# webcam_with_pan_tilt.net
KiCad netlist of a schematic drawn in EAGLE
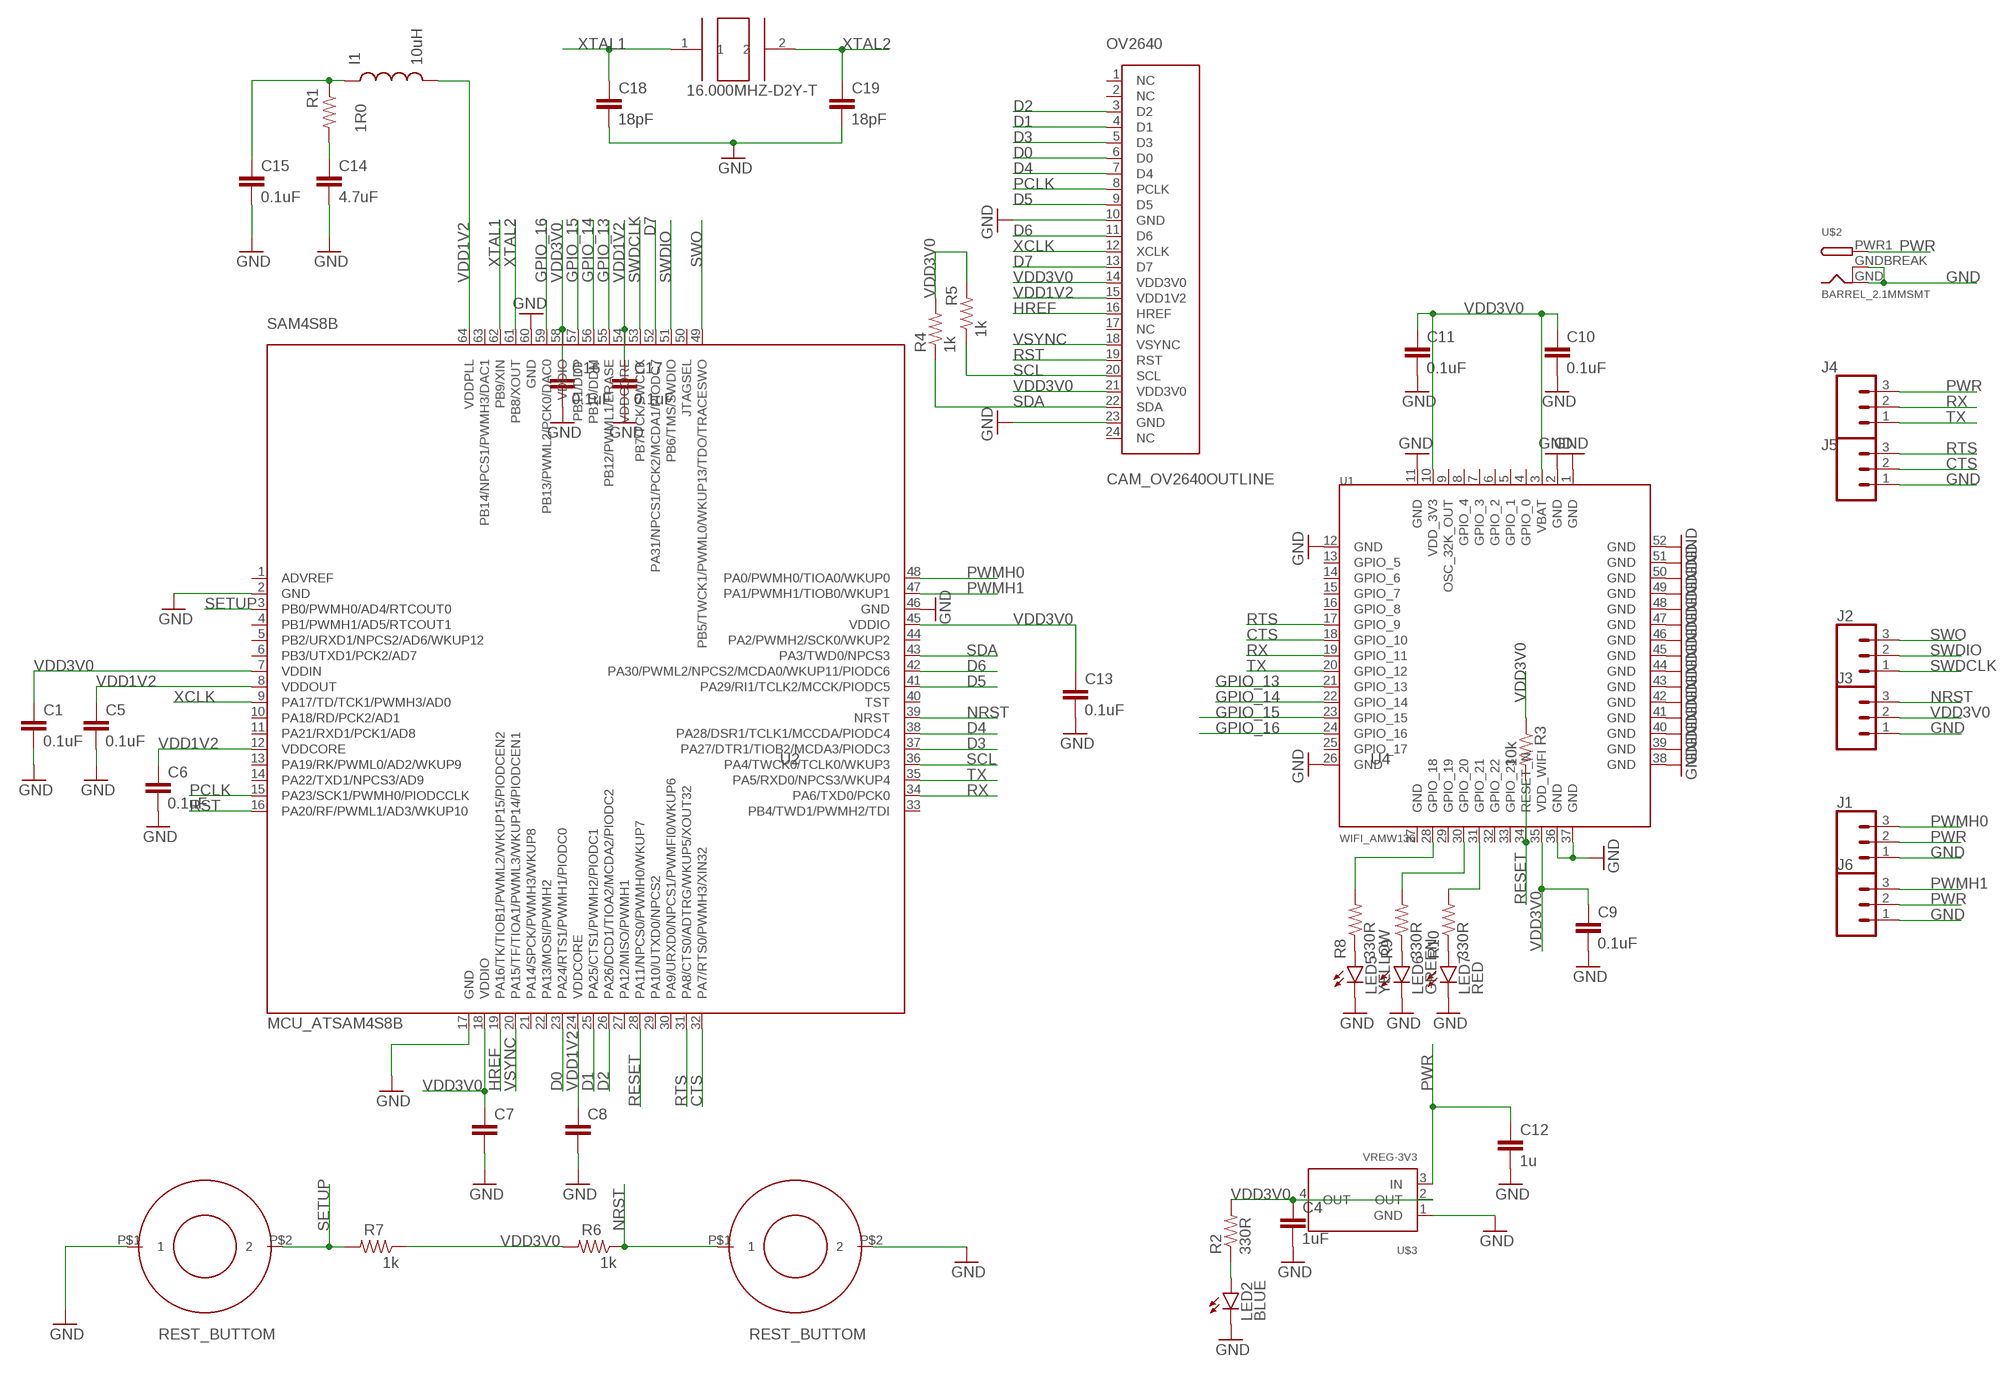
[diagram p0: schematic, sheet 1]

(export (version "E")
  (design (tool "Eeschema 10.0.6"))
  (components
    (comp (ref "16.000MHZ-D2Y-T")
      (value "XTAL_12MHZ")
      (footprint "eagle-import:ABM7-16.000MHZ-D2Y-T")
      (libsource (lib "eagle-import") (part "XTAL_12MHZ"))
    )
    (comp (ref "C1")
      (value "0.1uF")
      (footprint "eagle-import:0805")
      (libsource (lib "eagle-import") (part "CAP"))
    )
    (comp (ref "C4")
      (value "1uF")
      (footprint "eagle-import:0805")
      (libsource (lib "eagle-import") (part "CAP"))
    )
    (comp (ref "C5")
      (value "0.1uF")
      (footprint "eagle-import:0805")
      (libsource (lib "eagle-import") (part "CAP"))
    )
    (comp (ref "C6")
      (value "0.1uF")
      (footprint "eagle-import:0805")
      (libsource (lib "eagle-import") (part "CAP"))
    )
    (comp (ref "C7")
      (value "CAP")
      (footprint "eagle-import:0805")
      (libsource (lib "eagle-import") (part "CAP"))
    )
    (comp (ref "C8")
      (value "CAP")
      (footprint "eagle-import:0805")
      (libsource (lib "eagle-import") (part "CAP"))
    )
    (comp (ref "C9")
      (value "0.1uF")
      (footprint "eagle-import:0805")
      (libsource (lib "eagle-import") (part "CAP"))
    )
    (comp (ref "C10")
      (value "0.1uF")
      (footprint "eagle-import:0805")
      (libsource (lib "eagle-import") (part "CAP"))
    )
    (comp (ref "C11")
      (value "0.1uF")
      (footprint "eagle-import:0805")
      (libsource (lib "eagle-import") (part "CAP"))
    )
    (comp (ref "C12")
      (value "1u")
      (footprint "eagle-import:0805")
      (libsource (lib "eagle-import") (part "CAP"))
    )
    (comp (ref "C13")
      (value "0.1uF")
      (footprint "eagle-import:0805")
      (libsource (lib "eagle-import") (part "CAP"))
    )
    (comp (ref "C14")
      (value "4.7uF")
      (footprint "eagle-import:0805")
      (libsource (lib "eagle-import") (part "CAP"))
    )
    (comp (ref "C15")
      (value "0.1uF")
      (footprint "eagle-import:0805")
      (libsource (lib "eagle-import") (part "CAP"))
    )
    (comp (ref "C16")
      (value "0.1uF")
      (footprint "eagle-import:0805")
      (libsource (lib "eagle-import") (part "CAP"))
    )
    (comp (ref "C17")
      (value "0.1uF")
      (footprint "eagle-import:0805")
      (libsource (lib "eagle-import") (part "CAP"))
    )
    (comp (ref "C18")
      (value "18pF")
      (footprint "eagle-import:0805")
      (libsource (lib "eagle-import") (part "CAP"))
    )
    (comp (ref "C19")
      (value "18pF")
      (footprint "eagle-import:0805")
      (libsource (lib "eagle-import") (part "CAP"))
    )
    (comp (ref "I1")
      (value "10uH")
      (footprint "eagle-import:0805")
      (libsource (lib "eagle-import") (part "IND"))
    )
    (comp (ref "J1")
      (value "CONN_03")
      (footprint "eagle-import:1X03")
      (libsource (lib "eagle-import") (part "CONN_03"))
    )
    (comp (ref "J2")
      (value "CONN_03")
      (footprint "eagle-import:1X03")
      (libsource (lib "eagle-import") (part "CONN_03"))
    )
    (comp (ref "J3")
      (value "CONN_03")
      (footprint "eagle-import:1X03")
      (libsource (lib "eagle-import") (part "CONN_03"))
    )
    (comp (ref "J4")
      (value "CONN_03")
      (footprint "eagle-import:1X03")
      (libsource (lib "eagle-import") (part "CONN_03"))
    )
    (comp (ref "J5")
      (value "CONN_03")
      (footprint "eagle-import:1X03")
      (libsource (lib "eagle-import") (part "CONN_03"))
    )
    (comp (ref "J6")
      (value "CONN_03")
      (footprint "eagle-import:1X03")
      (libsource (lib "eagle-import") (part "CONN_03"))
    )
    (comp (ref "LED2")
      (value "BLUE")
      (footprint "eagle-import:LED-0603")
      (libsource (lib "eagle-import") (part "LED0603"))
    )
    (comp (ref "LED5")
      (value "YELLOW")
      (footprint "eagle-import:LED-0603")
      (libsource (lib "eagle-import") (part "LED0603"))
    )
    (comp (ref "LED6")
      (value "GREEN")
      (footprint "eagle-import:LED-0603")
      (libsource (lib "eagle-import") (part "LED0603"))
    )
    (comp (ref "LED7")
      (value "RED")
      (footprint "eagle-import:LED-0603")
      (libsource (lib "eagle-import") (part "LED0603"))
    )
    (comp (ref "OV2640")
      (value "CAM_OV2640OUTLINE")
      (footprint "eagle-import:CAM_CONN")
      (libsource (lib "eagle-import") (part "CAM_OV2640OUTLINE"))
    )
    (comp (ref "R1")
      (value "1R0")
      (footprint "eagle-import:0805")
      (libsource (lib "eagle-import") (part "RES"))
    )
    (comp (ref "R2")
      (value "330R")
      (footprint "eagle-import:0805")
      (libsource (lib "eagle-import") (part "RES"))
    )
    (comp (ref "R3")
      (value "10k")
      (footprint "eagle-import:0805")
      (libsource (lib "eagle-import") (part "RES"))
    )
    (comp (ref "R4")
      (value "1k")
      (footprint "eagle-import:0805")
      (libsource (lib "eagle-import") (part "RES"))
    )
    (comp (ref "R5")
      (value "1k")
      (footprint "eagle-import:0805")
      (libsource (lib "eagle-import") (part "RES"))
    )
    (comp (ref "R6")
      (value "1k")
      (footprint "eagle-import:0805")
      (libsource (lib "eagle-import") (part "RES"))
    )
    (comp (ref "R7")
      (value "1k")
      (footprint "eagle-import:0805")
      (libsource (lib "eagle-import") (part "RES"))
    )
    (comp (ref "R8")
      (value "330R")
      (footprint "eagle-import:0805")
      (libsource (lib "eagle-import") (part "RES"))
    )
    (comp (ref "R9")
      (value "330R")
      (footprint "eagle-import:0805")
      (libsource (lib "eagle-import") (part "RES"))
    )
    (comp (ref "R10")
      (value "330R")
      (footprint "eagle-import:0805")
      (libsource (lib "eagle-import") (part "RES"))
    )
    (comp (ref "SAM4S8B")
      (value "MCU_ATSAM4S8B")
      (footprint "eagle-import:QFP50P1200X1200X160-64N")
      (libsource (lib "eagle-import") (part "MCU_ATSAM4S8B"))
    )
    (comp (ref "U$2")
      (value "BARREL_2.1MMSMT")
      (footprint "eagle-import:DCJACK_2MM_SMT")
      (libsource (lib "eagle-import") (part "BARREL_2.1MMSMT"))
    )
    (comp (ref "U$3")
      (value "VREG-3V3")
      (footprint "eagle-import:R-PDSO-G4_TI")
      (libsource (lib "eagle-import") (part "VREG-3V3"))
    )
    (comp (ref "U1")
      (value "WIFI_AMW136")
      (footprint "eagle-import:AMW136")
      (libsource (lib "eagle-import") (part "WIFI_AMW136"))
    )
    (comp (ref "U2")
      (value "REST_BUTTOM")
      (footprint "eagle-import:BTN_2")
      (libsource (lib "eagle-import") (part "SWITCH_BTN_NO"))
    )
    (comp (ref "U4")
      (value "REST_BUTTOM")
      (footprint "eagle-import:BTN_2")
      (libsource (lib "eagle-import") (part "SWITCH_BTN_NO"))
    )
  )
  (nets
    (net (code "1") (name "/CTS") (class "Default")
      (node (ref "J5") (pin "2") (pinfunction "2_2") (pintype "passive"))
      (node (ref "SAM4S8B") (pin "32") (pinfunction "PA7/RTS0/PWMH3/XIN32_32") (pintype "bidirectional"))
      (node (ref "U1") (pin "18") (pinfunction "GPIO_10_18") (pintype "bidirectional"))
    )
    (net (code "2") (name "/D0") (class "Default")
      (node (ref "OV2640") (pin "6") (pinfunction "D0_6") (pintype "bidirectional"))
      (node (ref "SAM4S8B") (pin "23") (pinfunction "PA24/RTS1/PWMH1/PIODC0_23") (pintype "bidirectional"))
    )
    (net (code "3") (name "/D1") (class "Default")
      (node (ref "OV2640") (pin "4") (pinfunction "D1_4") (pintype "bidirectional"))
      (node (ref "SAM4S8B") (pin "25") (pinfunction "PA25/CTS1/PWMH2/PIODC1_25") (pintype "bidirectional"))
    )
    (net (code "4") (name "/D2") (class "Default")
      (node (ref "OV2640") (pin "3") (pinfunction "D2_3") (pintype "bidirectional"))
      (node (ref "SAM4S8B") (pin "26") (pinfunction "PA26/DCD1/TIOA2/MCDA2/PIODC2_26") (pintype "bidirectional"))
    )
    (net (code "5") (name "/D3") (class "Default")
      (node (ref "OV2640") (pin "5") (pinfunction "D3_5") (pintype "bidirectional"))
      (node (ref "SAM4S8B") (pin "37") (pinfunction "PA27/DTR1/TIOB2/MCDA3/PIODC3_37") (pintype "bidirectional"))
    )
    (net (code "6") (name "/D4") (class "Default")
      (node (ref "OV2640") (pin "7") (pinfunction "D4_7") (pintype "bidirectional"))
      (node (ref "SAM4S8B") (pin "38") (pinfunction "PA28/DSR1/TCLK1/MCCDA/PIODC4_38") (pintype "bidirectional"))
    )
    (net (code "7") (name "/D5") (class "Default")
      (node (ref "OV2640") (pin "9") (pinfunction "D5_9") (pintype "bidirectional"))
      (node (ref "SAM4S8B") (pin "41") (pinfunction "PA29/RI1/TCLK2/MCCK/PIODC5_41") (pintype "bidirectional"))
    )
    (net (code "8") (name "/D6") (class "Default")
      (node (ref "OV2640") (pin "11") (pinfunction "D6_11") (pintype "bidirectional"))
      (node (ref "SAM4S8B") (pin "42") (pinfunction "PA30/PWML2/NPCS2/MCDA0/WKUP11/PIODC6_42") (pintype "bidirectional"))
    )
    (net (code "9") (name "/D7") (class "Default")
      (node (ref "OV2640") (pin "13") (pinfunction "D7_13") (pintype "bidirectional"))
      (node (ref "SAM4S8B") (pin "52") (pinfunction "PA31/NPCS1/PCK2/MCDA1/PIODC7_52") (pintype "bidirectional"))
    )
    (net (code "10") (name "/GPIO_13") (class "Default")
      (node (ref "SAM4S8B") (pin "55") (pinfunction "PB12/PWML1/ERASE_55") (pintype "bidirectional"))
      (node (ref "U1") (pin "21") (pinfunction "GPIO_13_21") (pintype "bidirectional"))
    )
    (net (code "11") (name "/GPIO_14") (class "Default")
      (node (ref "SAM4S8B") (pin "56") (pinfunction "PB10/DDM_56") (pintype "bidirectional"))
      (node (ref "U1") (pin "22") (pinfunction "GPIO_14_22") (pintype "bidirectional"))
    )
    (net (code "12") (name "/GPIO_15") (class "Default")
      (node (ref "SAM4S8B") (pin "57") (pinfunction "PB11/DDP_57") (pintype "bidirectional"))
      (node (ref "U1") (pin "23") (pinfunction "GPIO_15_23") (pintype "bidirectional"))
    )
    (net (code "13") (name "/GPIO_16") (class "Default")
      (node (ref "SAM4S8B") (pin "59") (pinfunction "PB13/PWML2/PCK0/DAC0_59") (pintype "bidirectional"))
      (node (ref "U1") (pin "24") (pinfunction "GPIO_16_24") (pintype "bidirectional"))
    )
    (net (code "14") (name "/HREF") (class "Default")
      (node (ref "OV2640") (pin "16") (pinfunction "HREF_16") (pintype "bidirectional"))
      (node (ref "SAM4S8B") (pin "19") (pinfunction "PA16/TK/TIOB1/PWML2/WKUP15/PIODCEN2_19") (pintype "bidirectional"))
    )
    (net (code "15") (name "/NRST") (class "Default")
      (node (ref "J3") (pin "3") (pinfunction "3_3") (pintype "passive"))
      (node (ref "R6") (pin "1") (pinfunction "1_1") (pintype "passive"))
      (node (ref "SAM4S8B") (pin "39") (pinfunction "NRST_39") (pintype "bidirectional"))
      (node (ref "U4") (pin "P$1") (pinfunction "1_P$1") (pintype "bidirectional"))
    )
    (net (code "16") (name "/PCLK") (class "Default")
      (node (ref "OV2640") (pin "8") (pinfunction "PCLK_8") (pintype "bidirectional"))
      (node (ref "SAM4S8B") (pin "15") (pinfunction "PA23/SCK1/PWMH0/PIODCCLK_15") (pintype "bidirectional"))
    )
    (net (code "17") (name "/PWMH0") (class "Default")
      (node (ref "J1") (pin "3") (pinfunction "3_3") (pintype "passive"))
      (node (ref "SAM4S8B") (pin "48") (pinfunction "PA0/PWMH0/TIOA0/WKUP0_48") (pintype "bidirectional"))
    )
    (net (code "18") (name "/PWMH1") (class "Default")
      (node (ref "J6") (pin "3") (pinfunction "3_3") (pintype "passive"))
      (node (ref "SAM4S8B") (pin "47") (pinfunction "PA1/PWMH1/TIOB0/WKUP1_47") (pintype "bidirectional"))
    )
    (net (code "19") (name "/PWR") (class "Default")
      (node (ref "C12") (pin "1") (pinfunction "1_1") (pintype "passive"))
      (node (ref "J1") (pin "2") (pinfunction "2_2") (pintype "passive"))
      (node (ref "J4") (pin "3") (pinfunction "3_3") (pintype "passive"))
      (node (ref "J6") (pin "2") (pinfunction "2_2") (pintype "passive"))
      (node (ref "U$2") (pin "PWR1") (pinfunction "PWR_PWR1") (pintype "power_in"))
      (node (ref "U$3") (pin "3") (pinfunction "IN_3") (pintype "bidirectional"))
    )
    (net (code "20") (name "/RESET") (class "Default")
      (node (ref "R3") (pin "2") (pinfunction "2_2") (pintype "passive"))
      (node (ref "SAM4S8B") (pin "28") (pinfunction "PA11/NPCS0/PWMH0/WKUP7_28") (pintype "bidirectional"))
      (node (ref "U1") (pin "34") (pinfunction "RESET_N_34") (pintype "bidirectional"))
    )
    (net (code "21") (name "/RST") (class "Default")
      (node (ref "OV2640") (pin "19") (pinfunction "RST_19") (pintype "bidirectional"))
      (node (ref "SAM4S8B") (pin "16") (pinfunction "PA20/RF/PWML1/AD3/WKUP10_16") (pintype "bidirectional"))
    )
    (net (code "22") (name "/RTS") (class "Default")
      (node (ref "J5") (pin "3") (pinfunction "3_3") (pintype "passive"))
      (node (ref "SAM4S8B") (pin "31") (pinfunction "PA8/CTS0/ADTRG/WKUP5/XOUT32_31") (pintype "bidirectional"))
      (node (ref "U1") (pin "17") (pinfunction "GPIO_9_17") (pintype "bidirectional"))
    )
    (net (code "23") (name "/RX") (class "Default")
      (node (ref "J4") (pin "2") (pinfunction "2_2") (pintype "passive"))
      (node (ref "SAM4S8B") (pin "34") (pinfunction "PA6/TXD0/PCK0_34") (pintype "bidirectional"))
      (node (ref "U1") (pin "19") (pinfunction "GPIO_11_19") (pintype "bidirectional"))
    )
    (net (code "24") (name "/SCL") (class "Default")
      (node (ref "OV2640") (pin "20") (pinfunction "SCL_20") (pintype "bidirectional"))
      (node (ref "R5") (pin "1") (pinfunction "1_1") (pintype "passive"))
      (node (ref "SAM4S8B") (pin "36") (pinfunction "PA4/TWCK0/TCLK0/WKUP3_36") (pintype "bidirectional"))
    )
    (net (code "25") (name "/SDA") (class "Default")
      (node (ref "OV2640") (pin "22") (pinfunction "SDA_22") (pintype "bidirectional"))
      (node (ref "R4") (pin "1") (pinfunction "1_1") (pintype "passive"))
      (node (ref "SAM4S8B") (pin "43") (pinfunction "PA3/TWD0/NPCS3_43") (pintype "bidirectional"))
    )
    (net (code "26") (name "/SETUP") (class "Default")
      (node (ref "R7") (pin "2") (pinfunction "2_2") (pintype "passive"))
      (node (ref "SAM4S8B") (pin "3") (pinfunction "PB0/PWMH0/AD4/RTCOUT0_3") (pintype "bidirectional"))
      (node (ref "U2") (pin "P$2") (pinfunction "2_P$2") (pintype "bidirectional"))
    )
    (net (code "27") (name "/SWDCLK") (class "Default")
      (node (ref "J2") (pin "1") (pinfunction "1_1") (pintype "passive"))
      (node (ref "SAM4S8B") (pin "53") (pinfunction "PB7/TCK/SWCLK_53") (pintype "bidirectional"))
    )
    (net (code "28") (name "/SWDIO") (class "Default")
      (node (ref "J2") (pin "2") (pinfunction "2_2") (pintype "passive"))
      (node (ref "SAM4S8B") (pin "51") (pinfunction "PB6/TMS/SWDIO_51") (pintype "bidirectional"))
    )
    (net (code "29") (name "/SWO") (class "Default")
      (node (ref "J2") (pin "3") (pinfunction "3_3") (pintype "passive"))
      (node (ref "SAM4S8B") (pin "49") (pinfunction "PB5/TWCK1/PWML0/WKUP13/TDO/TRACESWO_49") (pintype "bidirectional"))
    )
    (net (code "30") (name "/TX") (class "Default")
      (node (ref "J4") (pin "1") (pinfunction "1_1") (pintype "passive"))
      (node (ref "SAM4S8B") (pin "35") (pinfunction "PA5/RXD0/NPCS3/WKUP4_35") (pintype "bidirectional"))
      (node (ref "U1") (pin "20") (pinfunction "GPIO_12_20") (pintype "bidirectional"))
    )
    (net (code "31") (name "/VDD1V2") (class "Default")
      (node (ref "C17") (pin "1") (pinfunction "1_1") (pintype "passive"))
      (node (ref "C5") (pin "1") (pinfunction "1_1") (pintype "passive"))
      (node (ref "C6") (pin "1") (pinfunction "1_1") (pintype "passive"))
      (node (ref "C8") (pin "1") (pinfunction "1_1") (pintype "passive"))
      (node (ref "I1") (pin "2") (pinfunction "2_2") (pintype "passive"))
      (node (ref "OV2640") (pin "15") (pinfunction "VDD1V2_15") (pintype "bidirectional"))
      (node (ref "SAM4S8B") (pin "12") (pinfunction "VDDCORE_12") (pintype "bidirectional"))
      (node (ref "SAM4S8B") (pin "24") (pinfunction "VDDCORE_24") (pintype "bidirectional"))
      (node (ref "SAM4S8B") (pin "54") (pinfunction "VDDCORE_54") (pintype "bidirectional"))
      (node (ref "SAM4S8B") (pin "64") (pinfunction "VDDPLL_64") (pintype "bidirectional"))
      (node (ref "SAM4S8B") (pin "8") (pinfunction "VDDOUT_8") (pintype "bidirectional"))
    )
    (net (code "32") (name "/VDD3V0") (class "Default")
      (node (ref "C1") (pin "1") (pinfunction "1_1") (pintype "passive"))
      (node (ref "C10") (pin "1") (pinfunction "1_1") (pintype "passive"))
      (node (ref "C11") (pin "1") (pinfunction "1_1") (pintype "passive"))
      (node (ref "C13") (pin "1") (pinfunction "1_1") (pintype "passive"))
      (node (ref "C16") (pin "1") (pinfunction "1_1") (pintype "passive"))
      (node (ref "C4") (pin "1") (pinfunction "1_1") (pintype "passive"))
      (node (ref "C7") (pin "1") (pinfunction "1_1") (pintype "passive"))
      (node (ref "C9") (pin "1") (pinfunction "1_1") (pintype "passive"))
      (node (ref "J3") (pin "2") (pinfunction "2_2") (pintype "passive"))
      (node (ref "OV2640") (pin "14") (pinfunction "VDD3V0_14") (pintype "bidirectional"))
      (node (ref "OV2640") (pin "21") (pinfunction "VDD3V0_21") (pintype "bidirectional"))
      (node (ref "R2") (pin "2") (pinfunction "2_2") (pintype "passive"))
      (node (ref "R3") (pin "1") (pinfunction "1_1") (pintype "passive"))
      (node (ref "R4") (pin "2") (pinfunction "2_2") (pintype "passive"))
      (node (ref "R5") (pin "2") (pinfunction "2_2") (pintype "passive"))
      (node (ref "R6") (pin "2") (pinfunction "2_2") (pintype "passive"))
      (node (ref "R7") (pin "1") (pinfunction "1_1") (pintype "passive"))
      (node (ref "SAM4S8B") (pin "18") (pinfunction "VDDIO_18") (pintype "bidirectional"))
      (node (ref "SAM4S8B") (pin "45") (pinfunction "VDDIO_45") (pintype "bidirectional"))
      (node (ref "SAM4S8B") (pin "58") (pinfunction "VDDIO_58") (pintype "bidirectional"))
      (node (ref "SAM4S8B") (pin "7") (pinfunction "VDDIN_7") (pintype "bidirectional"))
      (node (ref "U$3") (pin "2") (pinfunction "OUT_2") (pintype "bidirectional"))
      (node (ref "U$3") (pin "4") (pinfunction "OUT_4") (pintype "bidirectional"))
      (node (ref "U1") (pin "10") (pinfunction "VDD_3V3_10") (pintype "bidirectional"))
      (node (ref "U1") (pin "3") (pinfunction "VBAT_3") (pintype "bidirectional"))
      (node (ref "U1") (pin "35") (pinfunction "VDD_WIFI_35") (pintype "bidirectional"))
    )
    (net (code "33") (name "/VSYNC") (class "Default")
      (node (ref "OV2640") (pin "18") (pinfunction "VSYNC_18") (pintype "bidirectional"))
      (node (ref "SAM4S8B") (pin "20") (pinfunction "PA15/TF/TIOA1/PWML3/WKUP14/PIODCEN1_20") (pintype "bidirectional"))
    )
    (net (code "34") (name "/XCLK") (class "Default")
      (node (ref "OV2640") (pin "12") (pinfunction "XCLK_12") (pintype "bidirectional"))
      (node (ref "SAM4S8B") (pin "9") (pinfunction "PA17/TD/TCK1/PWMH3/AD0_9") (pintype "bidirectional"))
    )
    (net (code "35") (name "/XTAL1") (class "Default")
      (node (ref "16.000MHZ-D2Y-T") (pin "1") (pinfunction "1_1") (pintype "bidirectional"))
      (node (ref "C18") (pin "1") (pinfunction "1_1") (pintype "passive"))
      (node (ref "SAM4S8B") (pin "62") (pinfunction "PB9/XIN_62") (pintype "bidirectional"))
    )
    (net (code "36") (name "/XTAL2") (class "Default")
      (node (ref "16.000MHZ-D2Y-T") (pin "2") (pinfunction "2_2") (pintype "bidirectional"))
      (node (ref "C19") (pin "1") (pinfunction "1_1") (pintype "passive"))
      (node (ref "SAM4S8B") (pin "61") (pinfunction "PB8/XOUT_61") (pintype "bidirectional"))
    )
    (net (code "37") (name "GND") (class "Default")
      (node (ref "C1") (pin "2") (pinfunction "2_2") (pintype "passive"))
      (node (ref "C10") (pin "2") (pinfunction "2_2") (pintype "passive"))
      (node (ref "C11") (pin "2") (pinfunction "2_2") (pintype "passive"))
      (node (ref "C12") (pin "2") (pinfunction "2_2") (pintype "passive"))
      (node (ref "C13") (pin "2") (pinfunction "2_2") (pintype "passive"))
      (node (ref "C14") (pin "2") (pinfunction "2_2") (pintype "passive"))
      (node (ref "C15") (pin "2") (pinfunction "2_2") (pintype "passive"))
      (node (ref "C16") (pin "2") (pinfunction "2_2") (pintype "passive"))
      (node (ref "C17") (pin "2") (pinfunction "2_2") (pintype "passive"))
      (node (ref "C18") (pin "2") (pinfunction "2_2") (pintype "passive"))
      (node (ref "C19") (pin "2") (pinfunction "2_2") (pintype "passive"))
      (node (ref "C4") (pin "2") (pinfunction "2_2") (pintype "passive"))
      (node (ref "C5") (pin "2") (pinfunction "2_2") (pintype "passive"))
      (node (ref "C6") (pin "2") (pinfunction "2_2") (pintype "passive"))
      (node (ref "C7") (pin "2") (pinfunction "2_2") (pintype "passive"))
      (node (ref "C8") (pin "2") (pinfunction "2_2") (pintype "passive"))
      (node (ref "C9") (pin "2") (pinfunction "2_2") (pintype "passive"))
      (node (ref "J1") (pin "1") (pinfunction "1_1") (pintype "passive"))
      (node (ref "J3") (pin "1") (pinfunction "1_1") (pintype "passive"))
      (node (ref "J5") (pin "1") (pinfunction "1_1") (pintype "passive"))
      (node (ref "J6") (pin "1") (pinfunction "1_1") (pintype "passive"))
      (node (ref "LED2") (pin "C") (pinfunction "C_C") (pintype "passive"))
      (node (ref "LED5") (pin "C") (pinfunction "C_C") (pintype "passive"))
      (node (ref "LED6") (pin "C") (pinfunction "C_C") (pintype "passive"))
      (node (ref "LED7") (pin "C") (pinfunction "C_C") (pintype "passive"))
      (node (ref "OV2640") (pin "10") (pinfunction "GND_10") (pintype "bidirectional"))
      (node (ref "OV2640") (pin "23") (pinfunction "GND_23") (pintype "bidirectional"))
      (node (ref "SAM4S8B") (pin "17") (pinfunction "GND_17") (pintype "bidirectional"))
      (node (ref "SAM4S8B") (pin "2") (pinfunction "GND_2") (pintype "bidirectional"))
      (node (ref "SAM4S8B") (pin "46") (pinfunction "GND_46") (pintype "bidirectional"))
      (node (ref "SAM4S8B") (pin "60") (pinfunction "GND_60") (pintype "bidirectional"))
      (node (ref "U$2") (pin "GND") (pinfunction "GND_GND") (pintype "power_in"))
      (node (ref "U$2") (pin "GNDBREAK") (pinfunction "GNDBREAK_GNDBREAK") (pintype "power_in"))
      (node (ref "U$3") (pin "1") (pinfunction "GND_1") (pintype "bidirectional"))
      (node (ref "U1") (pin "1") (pinfunction "GND_1") (pintype "bidirectional"))
      (node (ref "U1") (pin "11") (pinfunction "GND_11") (pintype "bidirectional"))
      (node (ref "U1") (pin "12") (pinfunction "GND_12") (pintype "bidirectional"))
      (node (ref "U1") (pin "2") (pinfunction "GND_2") (pintype "bidirectional"))
      (node (ref "U1") (pin "26") (pinfunction "GND_26") (pintype "bidirectional"))
      (node (ref "U1") (pin "36") (pinfunction "GND_36") (pintype "bidirectional"))
      (node (ref "U1") (pin "37") (pinfunction "GND_37") (pintype "bidirectional"))
      (node (ref "U1") (pin "38") (pinfunction "GND_38") (pintype "bidirectional"))
      (node (ref "U1") (pin "39") (pinfunction "GND_39") (pintype "bidirectional"))
      (node (ref "U1") (pin "40") (pinfunction "GND_40") (pintype "bidirectional"))
      (node (ref "U1") (pin "41") (pinfunction "GND_41") (pintype "bidirectional"))
      (node (ref "U1") (pin "42") (pinfunction "GND_42") (pintype "bidirectional"))
      (node (ref "U1") (pin "43") (pinfunction "GND_43") (pintype "bidirectional"))
      (node (ref "U1") (pin "44") (pinfunction "GND_44") (pintype "bidirectional"))
      (node (ref "U1") (pin "45") (pinfunction "GND_45") (pintype "bidirectional"))
      (node (ref "U1") (pin "46") (pinfunction "GND_46") (pintype "bidirectional"))
      (node (ref "U1") (pin "47") (pinfunction "GND_47") (pintype "bidirectional"))
      (node (ref "U1") (pin "48") (pinfunction "GND_48") (pintype "bidirectional"))
      (node (ref "U1") (pin "49") (pinfunction "GND_49") (pintype "bidirectional"))
      (node (ref "U1") (pin "50") (pinfunction "GND_50") (pintype "bidirectional"))
      (node (ref "U1") (pin "51") (pinfunction "GND_51") (pintype "bidirectional"))
      (node (ref "U1") (pin "52") (pinfunction "GND_52") (pintype "bidirectional"))
      (node (ref "U2") (pin "P$1") (pinfunction "1_P$1") (pintype "bidirectional"))
      (node (ref "U4") (pin "P$2") (pinfunction "2_P$2") (pintype "bidirectional"))
    )
    (net (code "38") (name "Net-(C14-Pad1)") (class "Default")
      (node (ref "C14") (pin "1") (pinfunction "1_1") (pintype "passive"))
      (node (ref "R1") (pin "2") (pinfunction "2_2") (pintype "passive"))
    )
    (net (code "39") (name "Net-(C15-Pad1)") (class "Default")
      (node (ref "C15") (pin "1") (pinfunction "1_1") (pintype "passive"))
      (node (ref "I1") (pin "1") (pinfunction "1_1") (pintype "passive"))
      (node (ref "R1") (pin "1") (pinfunction "1_1") (pintype "passive"))
    )
    (net (code "40") (name "Net-(LED2-PadA)") (class "Default")
      (node (ref "LED2") (pin "A") (pinfunction "A_A") (pintype "passive"))
      (node (ref "R2") (pin "1") (pinfunction "1_1") (pintype "passive"))
    )
    (net (code "41") (name "Net-(LED5-PadA)") (class "Default")
      (node (ref "LED5") (pin "A") (pinfunction "A_A") (pintype "passive"))
      (node (ref "R8") (pin "1") (pinfunction "1_1") (pintype "passive"))
    )
    (net (code "42") (name "Net-(LED6-PadA)") (class "Default")
      (node (ref "LED6") (pin "A") (pinfunction "A_A") (pintype "passive"))
      (node (ref "R9") (pin "1") (pinfunction "1_1") (pintype "passive"))
    )
    (net (code "43") (name "Net-(LED7-PadA)") (class "Default")
      (node (ref "LED7") (pin "A") (pinfunction "A_A") (pintype "passive"))
      (node (ref "R10") (pin "1") (pinfunction "1_1") (pintype "passive"))
    )
    (net (code "44") (name "Net-(U1-GPIO_18)") (class "Default")
      (node (ref "R8") (pin "2") (pinfunction "2_2") (pintype "passive"))
      (node (ref "U1") (pin "28") (pinfunction "GPIO_18_28") (pintype "bidirectional"))
    )
    (net (code "45") (name "Net-(U1-GPIO_20)") (class "Default")
      (node (ref "R9") (pin "2") (pinfunction "2_2") (pintype "passive"))
      (node (ref "U1") (pin "30") (pinfunction "GPIO_20_30") (pintype "bidirectional"))
    )
    (net (code "46") (name "Net-(U1-GPIO_21)") (class "Default")
      (node (ref "R10") (pin "2") (pinfunction "2_2") (pintype "passive"))
      (node (ref "U1") (pin "31") (pinfunction "GPIO_21_31") (pintype "bidirectional"))
    )
    (net (code "47") (name "unconnected-(OV2640-NC-Pad1)") (class "Default")
      (node (ref "OV2640") (pin "1") (pinfunction "NC_1") (pintype "bidirectional"))
    )
    (net (code "48") (name "unconnected-(OV2640-NC-Pad2)") (class "Default")
      (node (ref "OV2640") (pin "2") (pinfunction "NC_2") (pintype "bidirectional"))
    )
    (net (code "49") (name "unconnected-(OV2640-NC-Pad17)") (class "Default")
      (node (ref "OV2640") (pin "17") (pinfunction "NC_17") (pintype "bidirectional"))
    )
    (net (code "50") (name "unconnected-(OV2640-NC-Pad24)") (class "Default")
      (node (ref "OV2640") (pin "24") (pinfunction "NC_24") (pintype "bidirectional"))
    )
    (net (code "51") (name "unconnected-(SAM4S8B-ADVREF-Pad1)") (class "Default")
      (node (ref "SAM4S8B") (pin "1") (pinfunction "ADVREF_1") (pintype "bidirectional"))
    )
    (net (code "52") (name "unconnected-(SAM4S8B-JTAGSEL-Pad50)") (class "Default")
      (node (ref "SAM4S8B") (pin "50") (pinfunction "JTAGSEL_50") (pintype "bidirectional"))
    )
    (net (code "53") (name "unconnected-(SAM4S8B-PA2{slash}PWMH2{slash}SCK0{slash}WKUP2-Pad44)") (class "Default")
      (node (ref "SAM4S8B") (pin "44") (pinfunction "PA2/PWMH2/SCK0/WKUP2_44") (pintype "bidirectional"))
    )
    (net (code "54") (name "unconnected-(SAM4S8B-PA9{slash}URXD0{slash}NPCS1{slash}PWMFI0{slash}WKUP6-Pad30)") (class "Default")
      (node (ref "SAM4S8B") (pin "30") (pinfunction "PA9/URXD0/NPCS1/PWMFI0/WKUP6_30") (pintype "bidirectional"))
    )
    (net (code "55") (name "unconnected-(SAM4S8B-PA10{slash}UTXD0{slash}NPCS2-Pad29)") (class "Default")
      (node (ref "SAM4S8B") (pin "29") (pinfunction "PA10/UTXD0/NPCS2_29") (pintype "bidirectional"))
    )
    (net (code "56") (name "unconnected-(SAM4S8B-PA12{slash}MISO{slash}PWMH1-Pad27)") (class "Default")
      (node (ref "SAM4S8B") (pin "27") (pinfunction "PA12/MISO/PWMH1_27") (pintype "bidirectional"))
    )
    (net (code "57") (name "unconnected-(SAM4S8B-PA13{slash}MOSI{slash}PWMH2-Pad22)") (class "Default")
      (node (ref "SAM4S8B") (pin "22") (pinfunction "PA13/MOSI/PWMH2_22") (pintype "bidirectional"))
    )
    (net (code "58") (name "unconnected-(SAM4S8B-PA14{slash}SPCK{slash}PWMH3{slash}WKUP8-Pad21)") (class "Default")
      (node (ref "SAM4S8B") (pin "21") (pinfunction "PA14/SPCK/PWMH3/WKUP8_21") (pintype "bidirectional"))
    )
    (net (code "59") (name "unconnected-(SAM4S8B-PA18{slash}RD{slash}PCK2{slash}AD1-Pad10)") (class "Default")
      (node (ref "SAM4S8B") (pin "10") (pinfunction "PA18/RD/PCK2/AD1_10") (pintype "bidirectional"))
    )
    (net (code "60") (name "unconnected-(SAM4S8B-PA19{slash}RK{slash}PWML0{slash}AD2{slash}WKUP9-Pad13)") (class "Default")
      (node (ref "SAM4S8B") (pin "13") (pinfunction "PA19/RK/PWML0/AD2/WKUP9_13") (pintype "bidirectional"))
    )
    (net (code "61") (name "unconnected-(SAM4S8B-PA21{slash}RXD1{slash}PCK1{slash}AD8-Pad11)") (class "Default")
      (node (ref "SAM4S8B") (pin "11") (pinfunction "PA21/RXD1/PCK1/AD8_11") (pintype "bidirectional"))
    )
    (net (code "62") (name "unconnected-(SAM4S8B-PA22{slash}TXD1{slash}NPCS3{slash}AD9-Pad14)") (class "Default")
      (node (ref "SAM4S8B") (pin "14") (pinfunction "PA22/TXD1/NPCS3/AD9_14") (pintype "bidirectional"))
    )
    (net (code "63") (name "unconnected-(SAM4S8B-PB1{slash}PWMH1{slash}AD5{slash}RTCOUT1-Pad4)") (class "Default")
      (node (ref "SAM4S8B") (pin "4") (pinfunction "PB1/PWMH1/AD5/RTCOUT1_4") (pintype "bidirectional"))
    )
    (net (code "64") (name "unconnected-(SAM4S8B-PB2{slash}URXD1{slash}NPCS2{slash}AD6{slash}WKUP12-Pad5)") (class "Default")
      (node (ref "SAM4S8B") (pin "5") (pinfunction "PB2/URXD1/NPCS2/AD6/WKUP12_5") (pintype "bidirectional"))
    )
    (net (code "65") (name "unconnected-(SAM4S8B-PB3{slash}UTXD1{slash}PCK2{slash}AD7-Pad6)") (class "Default")
      (node (ref "SAM4S8B") (pin "6") (pinfunction "PB3/UTXD1/PCK2/AD7_6") (pintype "bidirectional"))
    )
    (net (code "66") (name "unconnected-(SAM4S8B-PB4{slash}TWD1{slash}PWMH2{slash}TDI-Pad33)") (class "Default")
      (node (ref "SAM4S8B") (pin "33") (pinfunction "PB4/TWD1/PWMH2/TDI_33") (pintype "bidirectional"))
    )
    (net (code "67") (name "unconnected-(SAM4S8B-PB14{slash}NPCS1{slash}PWMH3{slash}DAC1-Pad63)") (class "Default")
      (node (ref "SAM4S8B") (pin "63") (pinfunction "PB14/NPCS1/PWMH3/DAC1_63") (pintype "bidirectional"))
    )
    (net (code "68") (name "unconnected-(SAM4S8B-TST-Pad40)") (class "Default")
      (node (ref "SAM4S8B") (pin "40") (pinfunction "TST_40") (pintype "bidirectional"))
    )
    (net (code "69") (name "unconnected-(U1-GND-Pad27)") (class "Default")
      (node (ref "U1") (pin "27") (pinfunction "GND_27") (pintype "bidirectional"))
    )
    (net (code "70") (name "unconnected-(U1-GPIO_0-Pad4)") (class "Default")
      (node (ref "U1") (pin "4") (pinfunction "GPIO_0_4") (pintype "bidirectional"))
    )
    (net (code "71") (name "unconnected-(U1-GPIO_1-Pad5)") (class "Default")
      (node (ref "U1") (pin "5") (pinfunction "GPIO_1_5") (pintype "bidirectional"))
    )
    (net (code "72") (name "unconnected-(U1-GPIO_2-Pad6)") (class "Default")
      (node (ref "U1") (pin "6") (pinfunction "GPIO_2_6") (pintype "bidirectional"))
    )
    (net (code "73") (name "unconnected-(U1-GPIO_3-Pad7)") (class "Default")
      (node (ref "U1") (pin "7") (pinfunction "GPIO_3_7") (pintype "bidirectional"))
    )
    (net (code "74") (name "unconnected-(U1-GPIO_4-Pad8)") (class "Default")
      (node (ref "U1") (pin "8") (pinfunction "GPIO_4_8") (pintype "bidirectional"))
    )
    (net (code "75") (name "unconnected-(U1-GPIO_5-Pad13)") (class "Default")
      (node (ref "U1") (pin "13") (pinfunction "GPIO_5_13") (pintype "bidirectional"))
    )
    (net (code "76") (name "unconnected-(U1-GPIO_6-Pad14)") (class "Default")
      (node (ref "U1") (pin "14") (pinfunction "GPIO_6_14") (pintype "bidirectional"))
    )
    (net (code "77") (name "unconnected-(U1-GPIO_7-Pad15)") (class "Default")
      (node (ref "U1") (pin "15") (pinfunction "GPIO_7_15") (pintype "bidirectional"))
    )
    (net (code "78") (name "unconnected-(U1-GPIO_8-Pad16)") (class "Default")
      (node (ref "U1") (pin "16") (pinfunction "GPIO_8_16") (pintype "bidirectional"))
    )
    (net (code "79") (name "unconnected-(U1-GPIO_17-Pad25)") (class "Default")
      (node (ref "U1") (pin "25") (pinfunction "GPIO_17_25") (pintype "bidirectional"))
    )
    (net (code "80") (name "unconnected-(U1-GPIO_19-Pad29)") (class "Default")
      (node (ref "U1") (pin "29") (pinfunction "GPIO_19_29") (pintype "bidirectional"))
    )
    (net (code "81") (name "unconnected-(U1-GPIO_22-Pad32)") (class "Default")
      (node (ref "U1") (pin "32") (pinfunction "GPIO_22_32") (pintype "bidirectional"))
    )
    (net (code "82") (name "unconnected-(U1-GPIO_23-Pad33)") (class "Default")
      (node (ref "U1") (pin "33") (pinfunction "GPIO_23_33") (pintype "bidirectional"))
    )
    (net (code "83") (name "unconnected-(U1-OSC_32K_OUT-Pad9)") (class "Default")
      (node (ref "U1") (pin "9") (pinfunction "OSC_32K_OUT_9") (pintype "bidirectional"))
    )
  )
)
